# MODULO_TECLADO.net
KiCad netlist of a schematic drawn in EAGLE
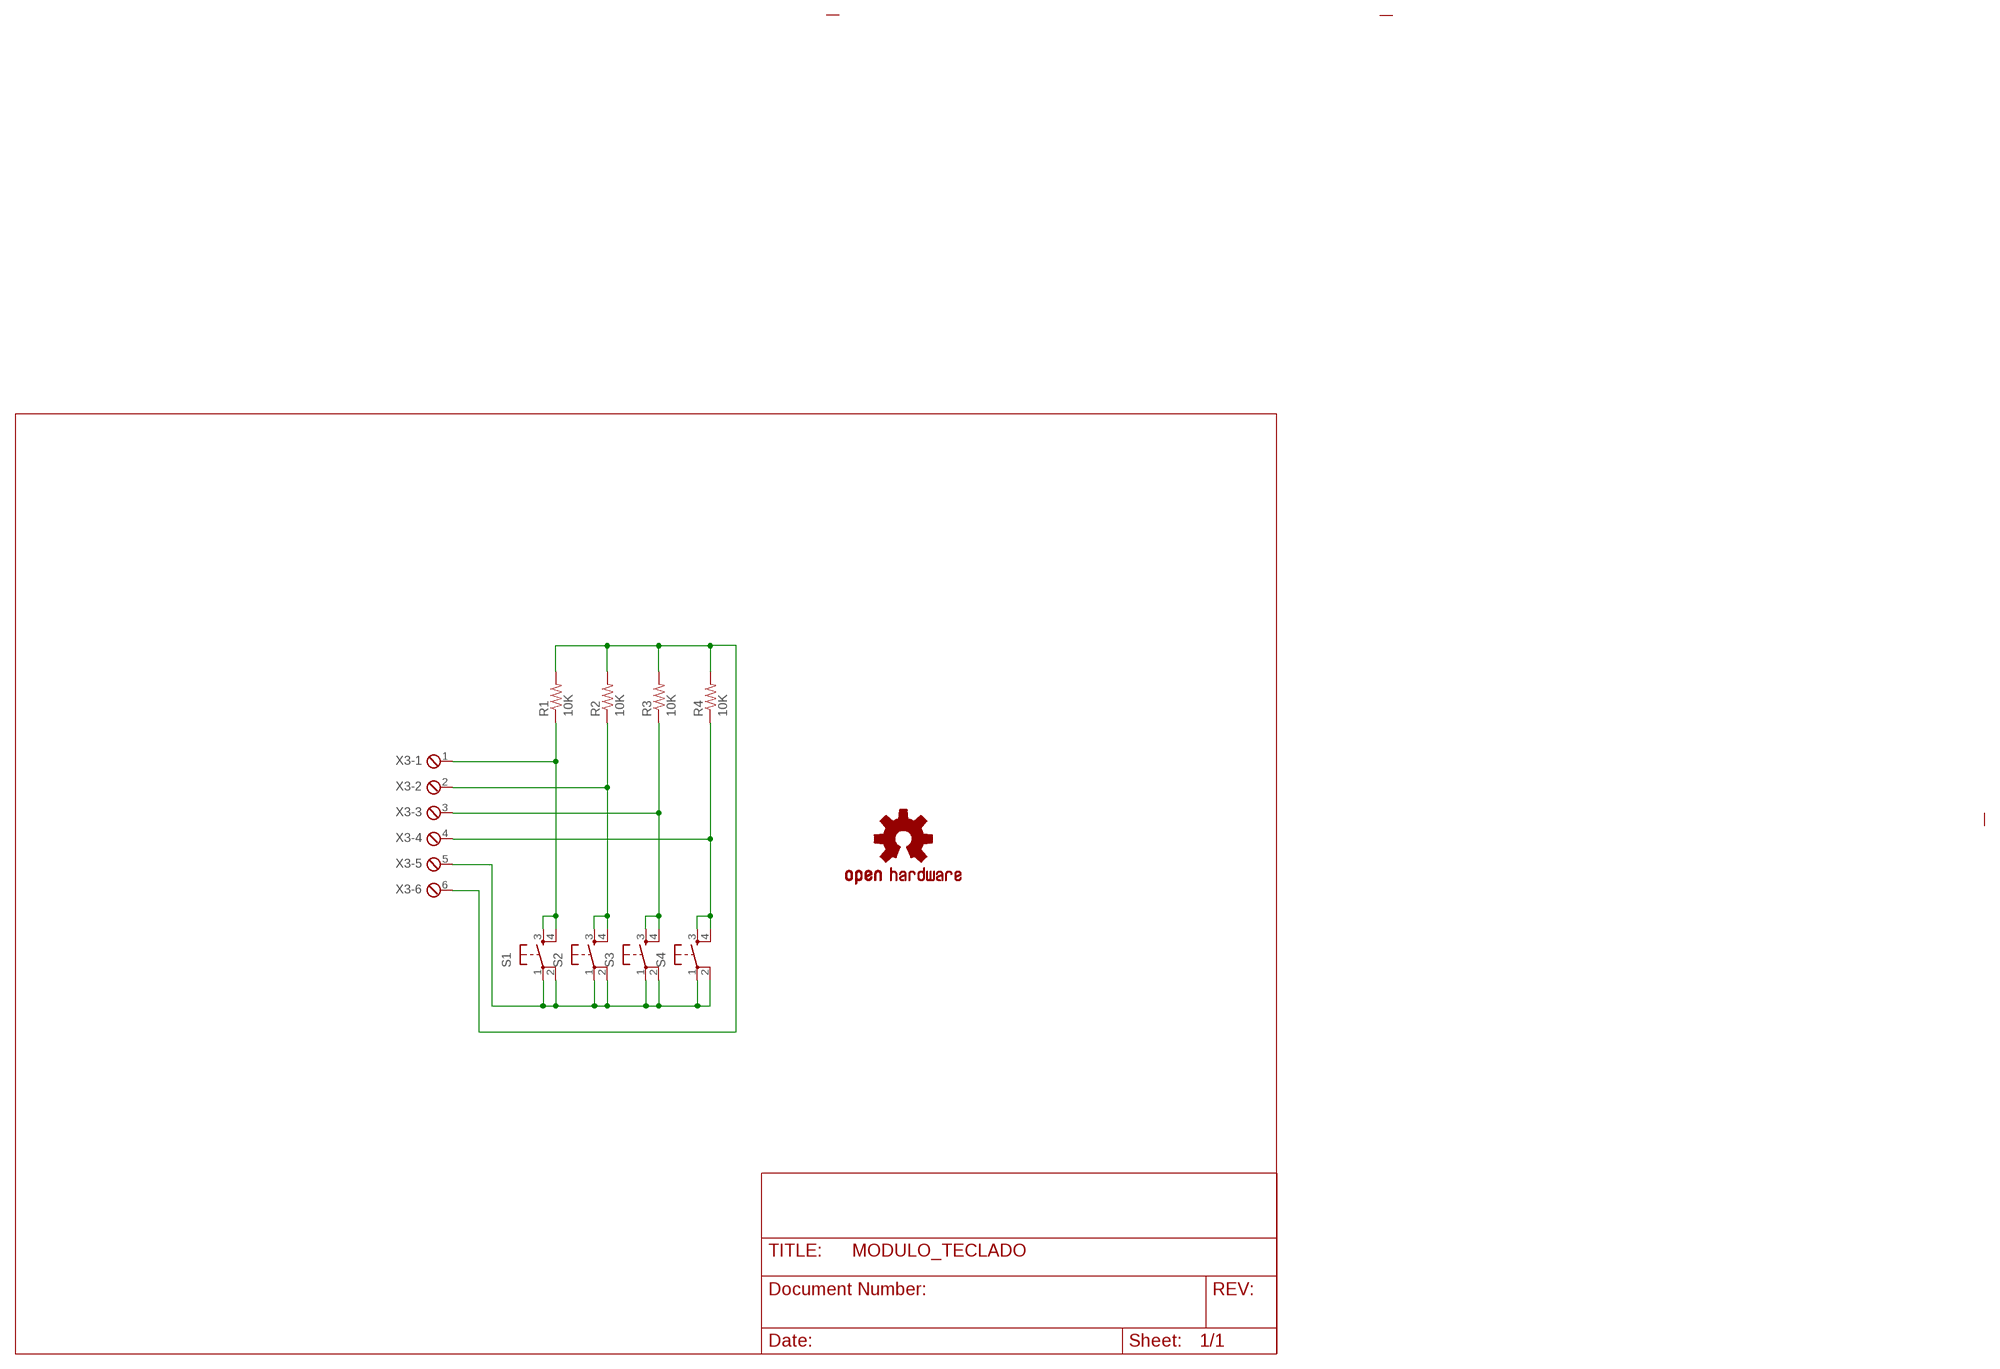
[diagram p0: schematic, sheet 1]

(export (version "E")
  (design (tool "Eeschema 10.0.6"))
  (components
    (comp (ref "LOGO1")
      (value "OSHW-LOGOM")
      (footprint "eagle-import:OSHW-LOGO-M")
      (libsource (lib "eagle-import") (part "OSHW-LOGOM"))
    )
    (comp (ref "R1")
      (value "10K")
      (footprint "eagle-import:AXIAL-0.4")
      (libsource (lib "eagle-import") (part "RESISTORPTH-1/4W"))
    )
    (comp (ref "R2")
      (value "10K")
      (footprint "eagle-import:AXIAL-0.4")
      (libsource (lib "eagle-import") (part "RESISTORPTH-1/4W"))
    )
    (comp (ref "R3")
      (value "10K")
      (footprint "eagle-import:AXIAL-0.4")
      (libsource (lib "eagle-import") (part "RESISTORPTH-1/4W"))
    )
    (comp (ref "R4")
      (value "10K")
      (footprint "eagle-import:AXIAL-0.4")
      (libsource (lib "eagle-import") (part "RESISTORPTH-1/4W"))
    )
    (comp (ref "S1")
      (value "TAC_SWITCHPTH")
      (footprint "eagle-import:TACTILE-PTH")
      (libsource (lib "eagle-import") (part "TAC_SWITCHPTH"))
    )
    (comp (ref "S2")
      (value "TAC_SWITCHPTH")
      (footprint "eagle-import:TACTILE-PTH")
      (libsource (lib "eagle-import") (part "TAC_SWITCHPTH"))
    )
    (comp (ref "S3")
      (value "TAC_SWITCHPTH")
      (footprint "eagle-import:TACTILE-PTH")
      (libsource (lib "eagle-import") (part "TAC_SWITCHPTH"))
    )
    (comp (ref "S4")
      (value "TAC_SWITCHPTH")
      (footprint "eagle-import:TACTILE-PTH")
      (libsource (lib "eagle-import") (part "TAC_SWITCHPTH"))
    )
    (comp (ref "X3")
      (value "MPT6")
      (footprint "eagle-import:6POL254")
      (libsource (lib "eagle-import") (part "MPT6"))
    )
  )
  (nets
    (net (code "1") (name "Net-(R1-1)") (class "Default")
      (node (ref "R1") (pin "P$1") (pinfunction "1_P$1") (pintype "passive"))
      (node (ref "S1") (pin "3") (pinfunction "3_3") (pintype "passive"))
      (node (ref "S1") (pin "4") (pinfunction "4_4") (pintype "passive"))
      (node (ref "X3") (pin "1") (pinfunction "1_1") (pintype "passive"))
    )
    (net (code "2") (name "Net-(R1-2)") (class "Default")
      (node (ref "R1") (pin "P$2") (pinfunction "2_P$2") (pintype "passive"))
      (node (ref "R2") (pin "P$2") (pinfunction "2_P$2") (pintype "passive"))
      (node (ref "R3") (pin "P$2") (pinfunction "2_P$2") (pintype "passive"))
      (node (ref "R4") (pin "P$2") (pinfunction "2_P$2") (pintype "passive"))
      (node (ref "X3") (pin "6") (pinfunction "1_6") (pintype "passive"))
    )
    (net (code "3") (name "Net-(R2-1)") (class "Default")
      (node (ref "R2") (pin "P$1") (pinfunction "1_P$1") (pintype "passive"))
      (node (ref "S2") (pin "3") (pinfunction "3_3") (pintype "passive"))
      (node (ref "S2") (pin "4") (pinfunction "4_4") (pintype "passive"))
      (node (ref "X3") (pin "2") (pinfunction "1_2") (pintype "passive"))
    )
    (net (code "4") (name "Net-(R3-1)") (class "Default")
      (node (ref "R3") (pin "P$1") (pinfunction "1_P$1") (pintype "passive"))
      (node (ref "S3") (pin "3") (pinfunction "3_3") (pintype "passive"))
      (node (ref "S3") (pin "4") (pinfunction "4_4") (pintype "passive"))
      (node (ref "X3") (pin "3") (pinfunction "1_3") (pintype "passive"))
    )
    (net (code "5") (name "Net-(R4-1)") (class "Default")
      (node (ref "R4") (pin "P$1") (pinfunction "1_P$1") (pintype "passive"))
      (node (ref "S4") (pin "3") (pinfunction "3_3") (pintype "passive"))
      (node (ref "S4") (pin "4") (pinfunction "4_4") (pintype "passive"))
      (node (ref "X3") (pin "4") (pinfunction "1_4") (pintype "passive"))
    )
    (net (code "6") (name "Net-(X3E-1)") (class "Default")
      (node (ref "S1") (pin "1") (pinfunction "1_1") (pintype "passive"))
      (node (ref "S1") (pin "2") (pinfunction "2_2") (pintype "passive"))
      (node (ref "S2") (pin "1") (pinfunction "1_1") (pintype "passive"))
      (node (ref "S2") (pin "2") (pinfunction "2_2") (pintype "passive"))
      (node (ref "S3") (pin "1") (pinfunction "1_1") (pintype "passive"))
      (node (ref "S3") (pin "2") (pinfunction "2_2") (pintype "passive"))
      (node (ref "S4") (pin "1") (pinfunction "1_1") (pintype "passive"))
      (node (ref "S4") (pin "2") (pinfunction "2_2") (pintype "passive"))
      (node (ref "X3") (pin "5") (pinfunction "1_5") (pintype "passive"))
    )
  )
)
